# QuadCurrentLoopCape.net
KiCad netlist of a schematic drawn in Altium Designer
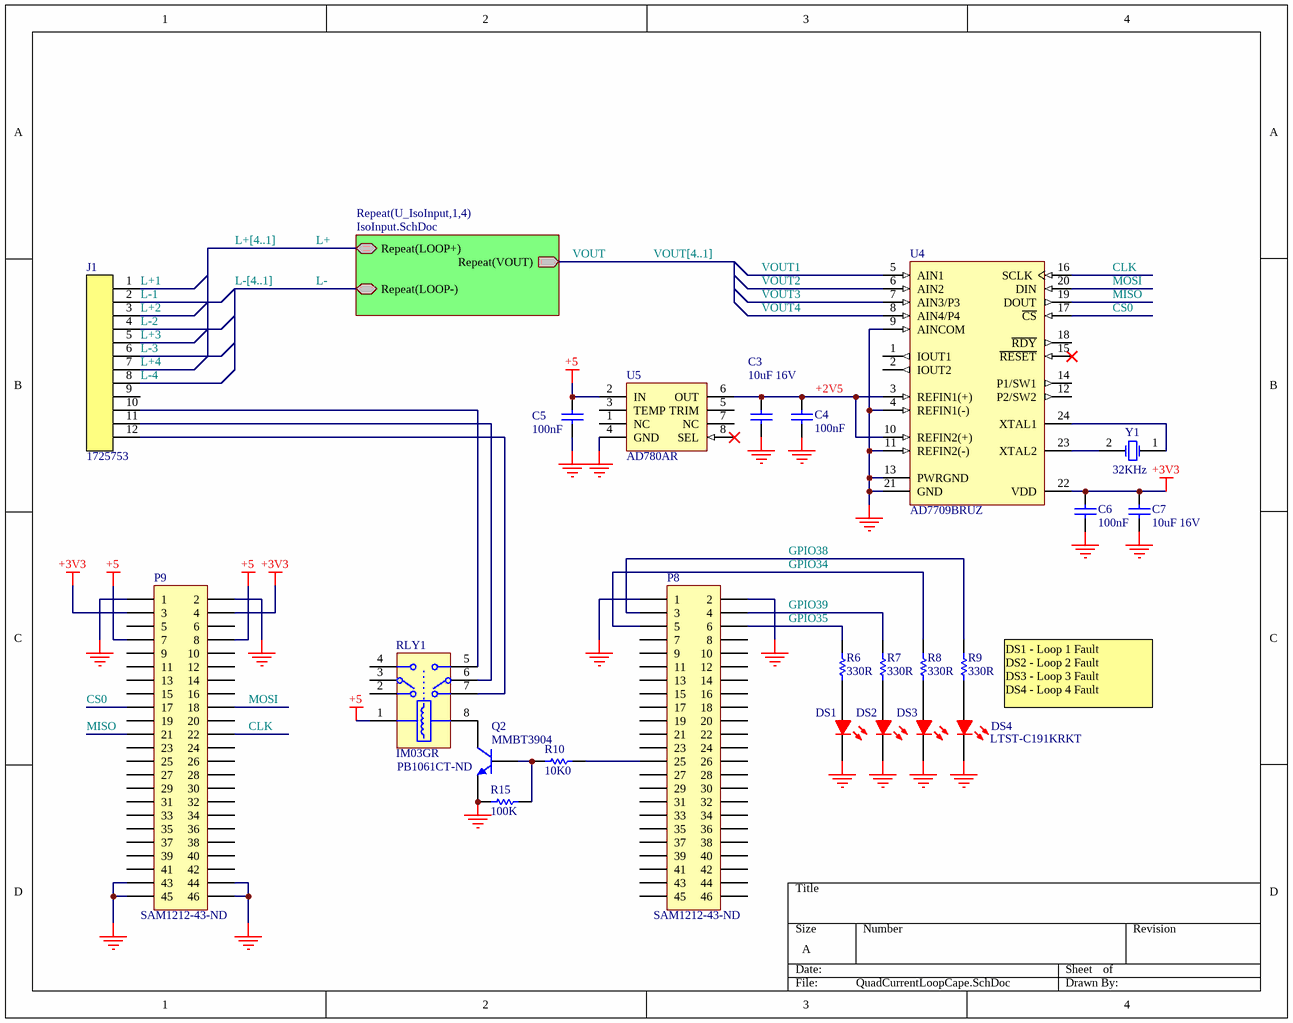
[diagram p0: QuadCurrentLoopCape.SchDoc]

(export (version "E")
  (design (tool "Eeschema 10.0.6"))
  (components
    (comp (ref "C3")
      (value "10uF 16V")
      (footprint "CAPC0805(2012)145_L")
      (description "CAP 10uF 16V ±20% 0805 (2012 Metric) Thickness 1.45mm SMD")
      (fields (field (name "TOLERANCE") "±20%"))
      (libsource (lib "Altium Content Vault") (part "CMP-1036-04929-1"))
    )
    (comp (ref "C4")
      (value "100nF")
      (footprint "CAPC0805(2012)100_L")
      (description "CAP 100nF 50V ±10% 0805 (2012 Metric) Thickness 1mm SMD")
      (fields (field (name "TOLERANCE") "±10%"))
      (libsource (lib "Altium Content Vault") (part "CMP-1036-04420-1"))
    )
    (comp (ref "C5")
      (value "100nF")
      (footprint "CAPC0805(2012)100_L")
      (description "CAP 100nF 50V ±10% 0805 (2012 Metric) Thickness 1mm SMD")
      (fields (field (name "TOLERANCE") "±10%"))
      (libsource (lib "Altium Content Vault") (part "CMP-1036-04420-1"))
    )
    (comp (ref "C6")
      (value "100nF")
      (footprint "CAPC0805(2012)100_L")
      (description "CAP 100nF 50V ±10% 0805 (2012 Metric) Thickness 1mm SMD")
      (fields (field (name "TOLERANCE") "±10%"))
      (libsource (lib "Altium Content Vault") (part "CMP-1036-04420-1"))
    )
    (comp (ref "C7")
      (value "10uF 16V")
      (footprint "CAPC0805(2012)145_L")
      (description "CAP 10uF 16V ±20% 0805 (2012 Metric) Thickness 1.45mm SMD")
      (fields (field (name "TOLERANCE") "±20%"))
      (libsource (lib "Altium Content Vault") (part "CMP-1036-04929-1"))
    )
    (comp (ref "DS1")
      (value "LTST-C191KRKT")
      (footprint "TOSH-0603LED_RED_V")
      (description "LED, Red 0603 (1608) 63mCd")
      (fields (field (name "MANUFACTURER") "Toshiba") (field (name "PARTNUMBER") "TLSU1008A(T04)"))
      (libsource (lib "Altium Content Vault") (part "CMP-0444-00001-1"))
    )
    (comp (ref "DS2")
      (value "LTST-C191KRKT")
      (footprint "TOSH-0603LED_RED_V")
      (description "LED, Red 0603 (1608) 63mCd")
      (fields (field (name "MANUFACTURER") "Toshiba") (field (name "PARTNUMBER") "TLSU1008A(T04)"))
      (libsource (lib "Altium Content Vault") (part "CMP-0444-00001-1"))
    )
    (comp (ref "DS3")
      (value "LTST-C191KRKT")
      (footprint "TOSH-0603LED_RED_V")
      (description "LED, Red 0603 (1608) 63mCd")
      (fields (field (name "MANUFACTURER") "Toshiba") (field (name "PARTNUMBER") "TLSU1008A(T04)"))
      (libsource (lib "Altium Content Vault") (part "CMP-0444-00001-1"))
    )
    (comp (ref "DS4")
      (value "LTST-C191KRKT")
      (footprint "TOSH-0603LED_RED_V")
      (description "LED, Red 0603 (1608) 63mCd")
      (fields (field (name "MANUFACTURER") "Toshiba") (field (name "PARTNUMBER") "TLSU1008A(T04)"))
      (libsource (lib "Altium Content Vault") (part "CMP-0444-00001-1"))
    )
    (comp (ref "J1")
      (value "1725753")
      (footprint "MPT0.5/12-2.54")
      (libsource (lib "MPT") (part "Pheonix12"))
    )
    (comp (ref "P8")
      (value "Header 23X2")
      (footprint "HDR2X23")
      (description "Header, 23-Pin, Dual Row")
      (fields (field (name "SUPPLIER PART NUMBER 1") "SAM1212-43-ND"))
      (libsource (lib "Miscellaneous Connectors") (part "Header 23X2"))
    )
    (comp (ref "P9")
      (value "Header 23X2")
      (footprint "HDR2X23")
      (description "Header, 23-Pin, Dual Row")
      (fields (field (name "SUPPLIER PART NUMBER 1") "SAM1212-43-ND"))
      (libsource (lib "Miscellaneous Connectors") (part "Header 23X2"))
    )
    (comp (ref "Q2")
      (value "MMBT3904")
      (footprint "SOT23_N")
      (description "NPN Switching Transistor")
      (fields (field (name "AML PART NUMBER") "TRN-S0002") (field (name "PUBLISHER") "Altium Limited"))
      (libsource (lib "Philips Discrete BJT - Low Power") (part "MMBT3904"))
    )
    (comp (ref "R6")
      (value "330R")
      (footprint "RESC0805(2012)_L")
      (description "330R 0.125W 1% 0805 (2012 Metric)  SMD")
      (fields (field (name "POWER") "0.125 W") (field (name "TOLERANCE") "1 %"))
      (libsource (lib "Altium Content Vault") (part "CMP-1013-00454-1"))
    )
    (comp (ref "R7")
      (value "330R")
      (footprint "RESC0805(2012)_L")
      (description "330R 0.125W 1% 0805 (2012 Metric)  SMD")
      (fields (field (name "POWER") "0.125 W") (field (name "TOLERANCE") "1 %"))
      (libsource (lib "Altium Content Vault") (part "CMP-1013-00454-1"))
    )
    (comp (ref "R8")
      (value "330R")
      (footprint "RESC0805(2012)_L")
      (description "330R 0.125W 1% 0805 (2012 Metric)  SMD")
      (fields (field (name "POWER") "0.125 W") (field (name "TOLERANCE") "1 %"))
      (libsource (lib "Altium Content Vault") (part "CMP-1013-00454-1"))
    )
    (comp (ref "R9")
      (value "330R")
      (footprint "RESC0805(2012)_L")
      (description "330R 0.125W 1% 0805 (2012 Metric)  SMD")
      (fields (field (name "POWER") "0.125 W") (field (name "TOLERANCE") "1 %"))
      (libsource (lib "Altium Content Vault") (part "CMP-1013-00454-1"))
    )
    (comp (ref "R10")
      (value "10K0")
      (footprint "RESC0603(1608)_L")
      (description "10K 0.1W 1% 0603 (1608 Metric)  SMD")
      (fields (field (name "POWER") "0.1 W") (field (name "TOLERANCE") "1 %"))
      (libsource (lib "Altium Content Vault") (part "CMP-1012-00623-1"))
    )
    (comp (ref "R15")
      (value "100K")
      (footprint "RESC0603(1608)_L")
      (description "100K 0.1W 1% 0603 (1608 Metric)  SMD")
      (fields (field (name "POWER") "0.1 W") (field (name "TOLERANCE") "1 %"))
      (libsource (lib "Altium Content Vault") (part "CMP-1012-00736-1"))
    )
    (comp (ref "RLY1")
      (value "IM03GR")
      (footprint "TECO-IM-8G-WING")
      (description "Low Power Consumption, High Dielectric, High Mechanical Shock Resistance, IM Relay")
      (fields
        (field (name "MANUFACTURER") "TE Connectivity")
        (field (name "SUPPLIER PART NUMBER 1") "PB1061CT-ND")
      )
      (libsource (lib "Altium Content Vault") (part "CMP-0439-00001-1"))
    )
    (comp (ref "U4")
      (value "AD7709BRUZ")
      (footprint "RU-24_L")
      (fields (field (name "MANUFACTURER") "Analog Devices") (field (name "GENERIC PART NUMBER") "AD7709"))
      (libsource (lib "Altium Content Vault") (part "CMP-0313-01986-2"))
    )
    (comp (ref "U5")
      (value "AD780AR")
      (footprint "R-8C_L")
      (description "2.5V/3.0V Ultrahigh Precision Bandgap Voltage Reference")
      (fields (field (name "PUBLISHER") "Altium Limited"))
      (libsource (lib "AD Power Mgt Voltage Reference") (part "AD780AR"))
    )
    (comp (ref "Y1")
      (value "32KHz")
      (footprint "CMR200T")
      (description "Crystal Oscillator")
      (fields (field (name "PUBLISHER") "Altium Limited"))
      (libsource (lib "Miscellaneous Devices") (part "XTAL"))
    )
  )
  (nets
    (net (code "1") (name "+3V3") (class "Default")
      (node (ref "C6") (pin "2") (pinfunction "2_2") (pintype "passive"))
      (node (ref "C7") (pin "2") (pinfunction "2_2") (pintype "passive"))
      (node (ref "P9") (pin "3") (pinfunction "3_3") (pintype "passive"))
      (node (ref "P9") (pin "4") (pinfunction "4_4") (pintype "passive"))
      (node (ref "U4") (pin "22") (pinfunction "VDD_22") (pintype "power_in"))
    )
    (net (code "2") (name "+5") (class "Default")
      (node (ref "C5") (pin "2") (pinfunction "2_2") (pintype "passive"))
      (node (ref "P9") (pin "7") (pinfunction "7_7") (pintype "passive"))
      (node (ref "P9") (pin "8") (pinfunction "8_8") (pintype "passive"))
      (node (ref "RLY1") (pin "1") (pinfunction "1_1") (pintype "passive"))
      (node (ref "U5") (pin "2") (pinfunction "IN_2") (pintype "power_in"))
    )
    (net (code "3") (name "/CLK") (class "Default")
      (node (ref "P9") (pin "22") (pinfunction "22_22") (pintype "passive"))
      (node (ref "U4") (pin "16") (pinfunction "SCLK_16") (pintype "input"))
    )
    (net (code "4") (name "/CS0") (class "Default")
      (node (ref "P9") (pin "17") (pinfunction "17_17") (pintype "passive"))
      (node (ref "U4") (pin "17") (pinfunction "~{CS}_17") (pintype "input"))
    )
    (net (code "5") (name "/GPIO34") (class "Default")
      (node (ref "P8") (pin "5") (pinfunction "5_5") (pintype "passive"))
      (node (ref "R8") (pin "2") (pinfunction "2_2") (pintype "passive"))
    )
    (net (code "6") (name "/GPIO35") (class "Default")
      (node (ref "P8") (pin "6") (pinfunction "6_6") (pintype "passive"))
      (node (ref "R6") (pin "2") (pinfunction "2_2") (pintype "passive"))
    )
    (net (code "7") (name "/GPIO38") (class "Default")
      (node (ref "P8") (pin "3") (pinfunction "3_3") (pintype "passive"))
      (node (ref "R9") (pin "2") (pinfunction "2_2") (pintype "passive"))
    )
    (net (code "8") (name "/GPIO39") (class "Default")
      (node (ref "P8") (pin "4") (pinfunction "4_4") (pintype "passive"))
      (node (ref "R7") (pin "2") (pinfunction "2_2") (pintype "passive"))
    )
    (net (code "10") (name "/L+1") (class "Default") (node (ref "J1") (pin "1") (pintype "passive")))
    (net (code "11") (name "/L+2") (class "Default") (node (ref "J1") (pin "3") (pintype "passive")))
    (net (code "12") (name "/L+3") (class "Default")
      (node (ref "J1") (pin "5") (pinfunction "5_5") (pintype "passive"))
    )
    (net (code "13") (name "/L+4") (class "Default")
      (node (ref "J1") (pin "7") (pinfunction "7_7") (pintype "passive"))
    )
    (net (code "16") (name "/L-1") (class "Default") (node (ref "J1") (pin "2") (pintype "passive")))
    (net (code "17") (name "/L-2") (class "Default") (node (ref "J1") (pin "4") (pintype "passive")))
    (net (code "18") (name "/L-3") (class "Default")
      (node (ref "J1") (pin "6") (pinfunction "6_6") (pintype "passive"))
    )
    (net (code "19") (name "/L-4") (class "Default")
      (node (ref "J1") (pin "8") (pinfunction "8_8") (pintype "passive"))
    )
    (net (code "21") (name "/MISO") (class "Default")
      (node (ref "P9") (pin "21") (pinfunction "21_21") (pintype "passive"))
      (node (ref "U4") (pin "19") (pinfunction "DOUT_19") (pintype "output"))
    )
    (net (code "22") (name "/MOSI") (class "Default")
      (node (ref "P9") (pin "18") (pinfunction "18_18") (pintype "passive"))
      (node (ref "U4") (pin "20") (pinfunction "DIN_20") (pintype "input"))
    )
    (net (code "24") (name "/VOUT1") (class "Default")
      (node (ref "U4") (pin "5") (pinfunction "AIN1_5") (pintype "input"))
    )
    (net (code "25") (name "/VOUT2") (class "Default")
      (node (ref "U4") (pin "6") (pinfunction "AIN2_6") (pintype "input"))
    )
    (net (code "26") (name "/VOUT3") (class "Default")
      (node (ref "U4") (pin "7") (pinfunction "AIN3/P3_7") (pintype "input"))
    )
    (net (code "27") (name "/VOUT4") (class "Default")
      (node (ref "U4") (pin "8") (pinfunction "AIN4/P4_8") (pintype "input"))
    )
    (net (code "29") (name "GND") (class "Default")
      (node (ref "C3") (pin "1") (pinfunction "1_1") (pintype "passive"))
      (node (ref "C4") (pin "1") (pinfunction "1_1") (pintype "passive"))
      (node (ref "C5") (pin "1") (pinfunction "1_1") (pintype "passive"))
      (node (ref "C6") (pin "1") (pinfunction "1_1") (pintype "passive"))
      (node (ref "C7") (pin "1") (pinfunction "1_1") (pintype "passive"))
      (node (ref "DS1") (pin "2") (pinfunction "K_2") (pintype "passive"))
      (node (ref "DS2") (pin "2") (pinfunction "K_2") (pintype "passive"))
      (node (ref "DS3") (pin "2") (pinfunction "K_2") (pintype "passive"))
      (node (ref "DS4") (pin "2") (pinfunction "K_2") (pintype "passive"))
      (node (ref "P8") (pin "1") (pinfunction "1_1") (pintype "passive"))
      (node (ref "P8") (pin "2") (pinfunction "2_2") (pintype "passive"))
      (node (ref "P9") (pin "1") (pinfunction "1_1") (pintype "passive"))
      (node (ref "P9") (pin "2") (pinfunction "2_2") (pintype "passive"))
      (node (ref "P9") (pin "43") (pinfunction "43_43") (pintype "passive"))
      (node (ref "P9") (pin "44") (pinfunction "44_44") (pintype "passive"))
      (node (ref "P9") (pin "45") (pinfunction "45_45") (pintype "passive"))
      (node (ref "P9") (pin "46") (pinfunction "46_46") (pintype "passive"))
      (node (ref "Q2") (pin "2") (pinfunction "E_2") (pintype "passive"))
      (node (ref "R15") (pin "2") (pinfunction "2_2") (pintype "passive"))
      (node (ref "U4") (pin "11") (pinfunction "REFIN2(-)_11") (pintype "input"))
      (node (ref "U4") (pin "13") (pinfunction "PWRGND_13") (pintype "power_in"))
      (node (ref "U4") (pin "21") (pinfunction "GND_21") (pintype "power_in"))
      (node (ref "U4") (pin "4") (pinfunction "REFIN1(-)_4") (pintype "input"))
      (node (ref "U4") (pin "9") (pinfunction "AINCOM_9") (pintype "input"))
      (node (ref "U5") (pin "4") (pinfunction "GND_4") (pintype "power_in"))
    )
    (net (code "30") (name "Net-(DS1-A)") (class "Default")
      (node (ref "DS1") (pin "1") (pinfunction "A_1") (pintype "passive"))
      (node (ref "R6") (pin "1") (pinfunction "1_1") (pintype "passive"))
    )
    (net (code "31") (name "Net-(DS2-A)") (class "Default")
      (node (ref "DS2") (pin "1") (pinfunction "A_1") (pintype "passive"))
      (node (ref "R7") (pin "1") (pinfunction "1_1") (pintype "passive"))
    )
    (net (code "32") (name "Net-(DS3-A)") (class "Default")
      (node (ref "DS3") (pin "1") (pinfunction "A_1") (pintype "passive"))
      (node (ref "R8") (pin "1") (pinfunction "1_1") (pintype "passive"))
    )
    (net (code "33") (name "Net-(DS4-A)") (class "Default")
      (node (ref "DS4") (pin "1") (pinfunction "A_1") (pintype "passive"))
      (node (ref "R9") (pin "1") (pinfunction "1_1") (pintype "passive"))
    )
    (net (code "34") (name "Net-(J1-Pad10)") (class "Default")
      (node (ref "J1") (pin "10") (pinfunction "10_10") (pintype "passive"))
      (node (ref "RLY1") (pin "5") (pinfunction "5_5") (pintype "passive"))
    )
    (net (code "35") (name "Net-(J1-Pad11)") (class "Default")
      (node (ref "J1") (pin "11") (pinfunction "11_11") (pintype "power_in"))
      (node (ref "RLY1") (pin "6") (pinfunction "6_6") (pintype "passive"))
    )
    (net (code "36") (name "Net-(J1-Pad12)") (class "Default")
      (node (ref "J1") (pin "12") (pinfunction "12_12") (pintype "power_in"))
      (node (ref "RLY1") (pin "7") (pinfunction "7_7") (pintype "passive"))
    )
    (net (code "37") (name "Net-(P8-Pad25)") (class "Default")
      (node (ref "P8") (pin "25") (pinfunction "25_25") (pintype "passive"))
      (node (ref "R10") (pin "2") (pinfunction "2_2") (pintype "passive"))
    )
    (net (code "38") (name "Net-(Q2-B)") (class "Default")
      (node (ref "Q2") (pin "1") (pinfunction "B_1") (pintype "passive"))
      (node (ref "R10") (pin "1") (pinfunction "1_1") (pintype "passive"))
      (node (ref "R15") (pin "1") (pinfunction "1_1") (pintype "passive"))
    )
    (net (code "39") (name "Net-(Q2-C)") (class "Default")
      (node (ref "Q2") (pin "3") (pinfunction "C_3") (pintype "passive"))
      (node (ref "RLY1") (pin "8") (pinfunction "8_8") (pintype "passive"))
    )
    (net (code "40") (name "Net-(U4-REFIN1(+))") (class "Default")
      (node (ref "C3") (pin "2") (pinfunction "2_2") (pintype "passive"))
      (node (ref "C4") (pin "2") (pinfunction "2_2") (pintype "passive"))
      (node (ref "U4") (pin "10") (pinfunction "REFIN2(+)_10") (pintype "input"))
      (node (ref "U4") (pin "3") (pinfunction "REFIN1(+)_3") (pintype "input"))
      (node (ref "U5") (pin "6") (pinfunction "OUT_6") (pintype "power_in"))
    )
    (net (code "41") (name "Net-(U4-XTAL1)") (class "Default")
      (node (ref "U4") (pin "24") (pinfunction "XTAL1_24") (pintype "passive"))
      (node (ref "Y1") (pin "1") (pinfunction "OSC1_1") (pintype "passive"))
    )
    (net (code "42") (name "Net-(U4-XTAL2)") (class "Default")
      (node (ref "U4") (pin "23") (pinfunction "XTAL2_23") (pintype "passive"))
      (node (ref "Y1") (pin "2") (pinfunction "OSC2_2") (pintype "passive"))
    )
    (net (code "43") (name "unconnected-(J1-Pad9)") (class "Default")
      (node (ref "J1") (pin "9") (pinfunction "9_9") (pintype "passive"))
    )
    (net (code "44") (name "unconnected-(P8-Pad7)") (class "Default")
      (node (ref "P8") (pin "7") (pinfunction "7_7") (pintype "passive"))
    )
    (net (code "45") (name "unconnected-(P8-Pad8)") (class "Default")
      (node (ref "P8") (pin "8") (pinfunction "8_8") (pintype "passive"))
    )
    (net (code "46") (name "unconnected-(P8-Pad9)") (class "Default")
      (node (ref "P8") (pin "9") (pinfunction "9_9") (pintype "passive"))
    )
    (net (code "47") (name "unconnected-(P8-Pad10)") (class "Default")
      (node (ref "P8") (pin "10") (pinfunction "10_10") (pintype "passive"))
    )
    (net (code "48") (name "unconnected-(P8-Pad11)") (class "Default")
      (node (ref "P8") (pin "11") (pinfunction "11_11") (pintype "passive"))
    )
    (net (code "49") (name "unconnected-(P8-Pad12)") (class "Default")
      (node (ref "P8") (pin "12") (pinfunction "12_12") (pintype "passive"))
    )
    (net (code "50") (name "unconnected-(P8-Pad13)") (class "Default")
      (node (ref "P8") (pin "13") (pinfunction "13_13") (pintype "passive"))
    )
    (net (code "51") (name "unconnected-(P8-Pad14)") (class "Default")
      (node (ref "P8") (pin "14") (pinfunction "14_14") (pintype "passive"))
    )
    (net (code "52") (name "unconnected-(P8-Pad15)") (class "Default")
      (node (ref "P8") (pin "15") (pinfunction "15_15") (pintype "passive"))
    )
    (net (code "53") (name "unconnected-(P8-Pad16)") (class "Default")
      (node (ref "P8") (pin "16") (pinfunction "16_16") (pintype "passive"))
    )
    (net (code "54") (name "unconnected-(P8-Pad17)") (class "Default")
      (node (ref "P8") (pin "17") (pinfunction "17_17") (pintype "passive"))
    )
    (net (code "55") (name "unconnected-(P8-Pad18)") (class "Default")
      (node (ref "P8") (pin "18") (pinfunction "18_18") (pintype "passive"))
    )
    (net (code "56") (name "unconnected-(P8-Pad19)") (class "Default")
      (node (ref "P8") (pin "19") (pinfunction "19_19") (pintype "passive"))
    )
    (net (code "57") (name "unconnected-(P8-Pad20)") (class "Default")
      (node (ref "P8") (pin "20") (pinfunction "20_20") (pintype "passive"))
    )
    (net (code "58") (name "unconnected-(P8-Pad21)") (class "Default")
      (node (ref "P8") (pin "21") (pinfunction "21_21") (pintype "passive"))
    )
    (net (code "59") (name "unconnected-(P8-Pad22)") (class "Default")
      (node (ref "P8") (pin "22") (pinfunction "22_22") (pintype "passive"))
    )
    (net (code "60") (name "unconnected-(P8-Pad23)") (class "Default")
      (node (ref "P8") (pin "23") (pinfunction "23_23") (pintype "passive"))
    )
    (net (code "61") (name "unconnected-(P8-Pad24)") (class "Default")
      (node (ref "P8") (pin "24") (pinfunction "24_24") (pintype "passive"))
    )
    (net (code "62") (name "unconnected-(P8-Pad26)") (class "Default")
      (node (ref "P8") (pin "26") (pinfunction "26_26") (pintype "passive"))
    )
    (net (code "63") (name "unconnected-(P8-Pad27)") (class "Default")
      (node (ref "P8") (pin "27") (pinfunction "27_27") (pintype "passive"))
    )
    (net (code "64") (name "unconnected-(P8-Pad28)") (class "Default")
      (node (ref "P8") (pin "28") (pinfunction "28_28") (pintype "passive"))
    )
    (net (code "65") (name "unconnected-(P8-Pad29)") (class "Default")
      (node (ref "P8") (pin "29") (pinfunction "29_29") (pintype "passive"))
    )
    (net (code "66") (name "unconnected-(P8-Pad30)") (class "Default")
      (node (ref "P8") (pin "30") (pinfunction "30_30") (pintype "passive"))
    )
    (net (code "67") (name "unconnected-(P8-Pad31)") (class "Default")
      (node (ref "P8") (pin "31") (pinfunction "31_31") (pintype "passive"))
    )
    (net (code "68") (name "unconnected-(P8-Pad32)") (class "Default")
      (node (ref "P8") (pin "32") (pinfunction "32_32") (pintype "passive"))
    )
    (net (code "69") (name "unconnected-(P8-Pad33)") (class "Default")
      (node (ref "P8") (pin "33") (pinfunction "33_33") (pintype "passive"))
    )
    (net (code "70") (name "unconnected-(P8-Pad34)") (class "Default")
      (node (ref "P8") (pin "34") (pinfunction "34_34") (pintype "passive"))
    )
    (net (code "71") (name "unconnected-(P8-Pad35)") (class "Default")
      (node (ref "P8") (pin "35") (pinfunction "35_35") (pintype "passive"))
    )
    (net (code "72") (name "unconnected-(P8-Pad36)") (class "Default")
      (node (ref "P8") (pin "36") (pinfunction "36_36") (pintype "passive"))
    )
    (net (code "73") (name "unconnected-(P8-Pad37)") (class "Default")
      (node (ref "P8") (pin "37") (pinfunction "37_37") (pintype "passive"))
    )
    (net (code "74") (name "unconnected-(P8-Pad38)") (class "Default")
      (node (ref "P8") (pin "38") (pinfunction "38_38") (pintype "passive"))
    )
    (net (code "75") (name "unconnected-(P8-Pad39)") (class "Default")
      (node (ref "P8") (pin "39") (pinfunction "39_39") (pintype "passive"))
    )
    (net (code "76") (name "unconnected-(P8-Pad40)") (class "Default")
      (node (ref "P8") (pin "40") (pinfunction "40_40") (pintype "passive"))
    )
    (net (code "77") (name "unconnected-(P8-Pad41)") (class "Default")
      (node (ref "P8") (pin "41") (pinfunction "41_41") (pintype "passive"))
    )
    (net (code "78") (name "unconnected-(P8-Pad42)") (class "Default")
      (node (ref "P8") (pin "42") (pinfunction "42_42") (pintype "passive"))
    )
    (net (code "79") (name "unconnected-(P8-Pad43)") (class "Default")
      (node (ref "P8") (pin "43") (pinfunction "43_43") (pintype "passive"))
    )
    (net (code "80") (name "unconnected-(P8-Pad44)") (class "Default")
      (node (ref "P8") (pin "44") (pinfunction "44_44") (pintype "passive"))
    )
    (net (code "81") (name "unconnected-(P8-Pad45)") (class "Default")
      (node (ref "P8") (pin "45") (pinfunction "45_45") (pintype "passive"))
    )
    (net (code "82") (name "unconnected-(P8-Pad46)") (class "Default")
      (node (ref "P8") (pin "46") (pinfunction "46_46") (pintype "passive"))
    )
    (net (code "83") (name "unconnected-(P9-Pad5)") (class "Default")
      (node (ref "P9") (pin "5") (pinfunction "5_5") (pintype "passive"))
    )
    (net (code "84") (name "unconnected-(P9-Pad6)") (class "Default")
      (node (ref "P9") (pin "6") (pinfunction "6_6") (pintype "passive"))
    )
    (net (code "85") (name "unconnected-(P9-Pad9)") (class "Default")
      (node (ref "P9") (pin "9") (pinfunction "9_9") (pintype "passive"))
    )
    (net (code "86") (name "unconnected-(P9-Pad10)") (class "Default")
      (node (ref "P9") (pin "10") (pinfunction "10_10") (pintype "passive"))
    )
    (net (code "87") (name "unconnected-(P9-Pad11)") (class "Default")
      (node (ref "P9") (pin "11") (pinfunction "11_11") (pintype "passive"))
    )
    (net (code "88") (name "unconnected-(P9-Pad12)") (class "Default")
      (node (ref "P9") (pin "12") (pinfunction "12_12") (pintype "passive"))
    )
    (net (code "89") (name "unconnected-(P9-Pad13)") (class "Default")
      (node (ref "P9") (pin "13") (pinfunction "13_13") (pintype "passive"))
    )
    (net (code "90") (name "unconnected-(P9-Pad14)") (class "Default")
      (node (ref "P9") (pin "14") (pinfunction "14_14") (pintype "passive"))
    )
    (net (code "91") (name "unconnected-(P9-Pad15)") (class "Default")
      (node (ref "P9") (pin "15") (pinfunction "15_15") (pintype "passive"))
    )
    (net (code "92") (name "unconnected-(P9-Pad16)") (class "Default")
      (node (ref "P9") (pin "16") (pinfunction "16_16") (pintype "passive"))
    )
    (net (code "93") (name "unconnected-(P9-Pad19)") (class "Default")
      (node (ref "P9") (pin "19") (pinfunction "19_19") (pintype "passive"))
    )
    (net (code "94") (name "unconnected-(P9-Pad20)") (class "Default")
      (node (ref "P9") (pin "20") (pinfunction "20_20") (pintype "passive"))
    )
    (net (code "95") (name "unconnected-(P9-Pad23)") (class "Default")
      (node (ref "P9") (pin "23") (pinfunction "23_23") (pintype "passive"))
    )
    (net (code "96") (name "unconnected-(P9-Pad24)") (class "Default")
      (node (ref "P9") (pin "24") (pinfunction "24_24") (pintype "passive"))
    )
    (net (code "97") (name "unconnected-(P9-Pad25)") (class "Default")
      (node (ref "P9") (pin "25") (pinfunction "25_25") (pintype "passive"))
    )
    (net (code "98") (name "unconnected-(P9-Pad26)") (class "Default")
      (node (ref "P9") (pin "26") (pinfunction "26_26") (pintype "passive"))
    )
    (net (code "99") (name "unconnected-(P9-Pad27)") (class "Default")
      (node (ref "P9") (pin "27") (pinfunction "27_27") (pintype "passive"))
    )
    (net (code "100") (name "unconnected-(P9-Pad28)") (class "Default")
      (node (ref "P9") (pin "28") (pinfunction "28_28") (pintype "passive"))
    )
    (net (code "101") (name "unconnected-(P9-Pad29)") (class "Default")
      (node (ref "P9") (pin "29") (pinfunction "29_29") (pintype "passive"))
    )
    (net (code "102") (name "unconnected-(P9-Pad30)") (class "Default")
      (node (ref "P9") (pin "30") (pinfunction "30_30") (pintype "passive"))
    )
    (net (code "103") (name "unconnected-(P9-Pad31)") (class "Default")
      (node (ref "P9") (pin "31") (pinfunction "31_31") (pintype "passive"))
    )
    (net (code "104") (name "unconnected-(P9-Pad32)") (class "Default")
      (node (ref "P9") (pin "32") (pinfunction "32_32") (pintype "passive"))
    )
    (net (code "105") (name "unconnected-(P9-Pad33)") (class "Default")
      (node (ref "P9") (pin "33") (pinfunction "33_33") (pintype "passive"))
    )
    (net (code "106") (name "unconnected-(P9-Pad34)") (class "Default")
      (node (ref "P9") (pin "34") (pinfunction "34_34") (pintype "passive"))
    )
    (net (code "107") (name "unconnected-(P9-Pad35)") (class "Default")
      (node (ref "P9") (pin "35") (pinfunction "35_35") (pintype "passive"))
    )
    (net (code "108") (name "unconnected-(P9-Pad36)") (class "Default")
      (node (ref "P9") (pin "36") (pinfunction "36_36") (pintype "passive"))
    )
    (net (code "109") (name "unconnected-(P9-Pad37)") (class "Default")
      (node (ref "P9") (pin "37") (pinfunction "37_37") (pintype "passive"))
    )
    (net (code "110") (name "unconnected-(P9-Pad38)") (class "Default")
      (node (ref "P9") (pin "38") (pinfunction "38_38") (pintype "passive"))
    )
    (net (code "111") (name "unconnected-(P9-Pad39)") (class "Default")
      (node (ref "P9") (pin "39") (pinfunction "39_39") (pintype "passive"))
    )
    (net (code "112") (name "unconnected-(P9-Pad40)") (class "Default")
      (node (ref "P9") (pin "40") (pinfunction "40_40") (pintype "passive"))
    )
    (net (code "113") (name "unconnected-(P9-Pad41)") (class "Default")
      (node (ref "P9") (pin "41") (pinfunction "41_41") (pintype "passive"))
    )
    (net (code "114") (name "unconnected-(P9-Pad42)") (class "Default")
      (node (ref "P9") (pin "42") (pinfunction "42_42") (pintype "passive"))
    )
    (net (code "115") (name "unconnected-(RLY1-Pad2)") (class "Default")
      (node (ref "RLY1") (pin "2") (pinfunction "2_2") (pintype "passive"))
    )
    (net (code "116") (name "unconnected-(RLY1-Pad3)") (class "Default")
      (node (ref "RLY1") (pin "3") (pinfunction "3_3") (pintype "passive"))
    )
    (net (code "117") (name "unconnected-(RLY1-Pad4)") (class "Default")
      (node (ref "RLY1") (pin "4") (pinfunction "4_4") (pintype "passive"))
    )
    (net (code "118") (name "unconnected-(U4-IOUT1-Pad1)") (class "Default")
      (node (ref "U4") (pin "1") (pinfunction "IOUT1_1") (pintype "output"))
    )
    (net (code "119") (name "unconnected-(U4-IOUT2-Pad2)") (class "Default")
      (node (ref "U4") (pin "2") (pinfunction "IOUT2_2") (pintype "output"))
    )
    (net (code "120") (name "unconnected-(U4-P1{slash}SW1-Pad14)") (class "Default")
      (node (ref "U4") (pin "14") (pinfunction "P1/SW1_14") (pintype "output"))
    )
    (net (code "121") (name "unconnected-(U4-P2{slash}SW2-Pad12)") (class "Default")
      (node (ref "U4") (pin "12") (pinfunction "P2/SW2_12") (pintype "output"))
    )
    (net (code "122") (name "unconnected-(U4-~{RDY}-Pad18)") (class "Default")
      (node (ref "U4") (pin "18") (pinfunction "~{RDY}_18") (pintype "output"))
    )
    (net (code "123") (name "unconnected-(U4-~{RESET}-Pad15)") (class "Default")
      (node (ref "U4") (pin "15") (pinfunction "~{RESET}_15") (pintype "input+no_connect"))
    )
    (net (code "124") (name "unconnected-(U5-NC-Pad1)") (class "Default")
      (node (ref "U5") (pin "1") (pinfunction "NC_1") (pintype "passive"))
    )
    (net (code "125") (name "unconnected-(U5-NC-Pad7)") (class "Default")
      (node (ref "U5") (pin "7") (pinfunction "NC_7") (pintype "passive"))
    )
    (net (code "126") (name "unconnected-(U5-SEL-Pad8)") (class "Default")
      (node (ref "U5") (pin "8") (pinfunction "SEL_8") (pintype "input+no_connect"))
    )
    (net (code "127") (name "unconnected-(U5-TEMP-Pad3)") (class "Default")
      (node (ref "U5") (pin "3") (pinfunction "TEMP_3") (pintype "passive"))
    )
    (net (code "128") (name "unconnected-(U5-TRIM-Pad5)") (class "Default")
      (node (ref "U5") (pin "5") (pinfunction "TRIM_5") (pintype "passive"))
    )
  )
)
